# ploza.net
KiCad netlist of a schematic drawn in EAGLE
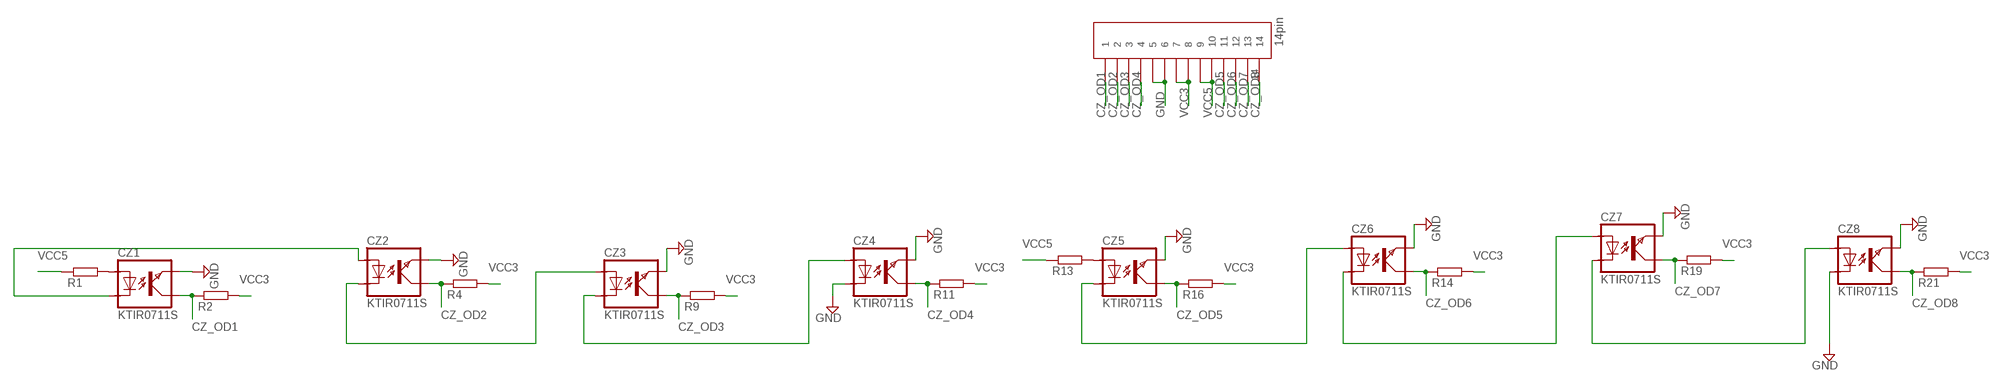
[diagram p0: schematic, sheet 1]

(export (version "E")
  (design (tool "Eeschema 10.0.6"))
  (components
    (comp (ref "CZ1")
      (value "KTIR0711S")
      (footprint "eagle-import:TOP")
      (libsource (lib "eagle-import") (part "KTIR0711S"))
    )
    (comp (ref "CZ2")
      (value "KTIR0711S")
      (footprint "eagle-import:TOP")
      (libsource (lib "eagle-import") (part "KTIR0711S"))
    )
    (comp (ref "CZ3")
      (value "KTIR0711S")
      (footprint "eagle-import:TOP")
      (libsource (lib "eagle-import") (part "KTIR0711S"))
    )
    (comp (ref "CZ4")
      (value "KTIR0711S")
      (footprint "eagle-import:TOP")
      (libsource (lib "eagle-import") (part "KTIR0711S"))
    )
    (comp (ref "CZ5")
      (value "KTIR0711S")
      (footprint "eagle-import:TOP")
      (libsource (lib "eagle-import") (part "KTIR0711S"))
    )
    (comp (ref "CZ6")
      (value "KTIR0711S")
      (footprint "eagle-import:TOP")
      (libsource (lib "eagle-import") (part "KTIR0711S"))
    )
    (comp (ref "CZ7")
      (value "KTIR0711S")
      (footprint "eagle-import:TOP")
      (libsource (lib "eagle-import") (part "KTIR0711S"))
    )
    (comp (ref "CZ8")
      (value "KTIR0711S")
      (footprint "eagle-import:TOP")
      (libsource (lib "eagle-import") (part "KTIR0711S"))
    )
    (comp (ref "R1")
      (value "R-EU_R0805")
      (footprint "eagle-import:R0805")
      (libsource (lib "eagle-import") (part "R-EU_R0805"))
    )
    (comp (ref "R2")
      (value "R-EU_R0805")
      (footprint "eagle-import:R0805")
      (libsource (lib "eagle-import") (part "R-EU_R0805"))
    )
    (comp (ref "R4")
      (value "R-EU_R0805")
      (footprint "eagle-import:R0805")
      (libsource (lib "eagle-import") (part "R-EU_R0805"))
    )
    (comp (ref "R9")
      (value "R-EU_R0805")
      (footprint "eagle-import:R0805")
      (libsource (lib "eagle-import") (part "R-EU_R0805"))
    )
    (comp (ref "R11")
      (value "R-EU_R0805")
      (footprint "eagle-import:R0805")
      (libsource (lib "eagle-import") (part "R-EU_R0805"))
    )
    (comp (ref "R13")
      (value "R-EU_R0805")
      (footprint "eagle-import:R0805")
      (libsource (lib "eagle-import") (part "R-EU_R0805"))
    )
    (comp (ref "R14")
      (value "R-EU_R0805")
      (footprint "eagle-import:R0805")
      (libsource (lib "eagle-import") (part "R-EU_R0805"))
    )
    (comp (ref "R16")
      (value "R-EU_R0805")
      (footprint "eagle-import:R0805")
      (libsource (lib "eagle-import") (part "R-EU_R0805"))
    )
    (comp (ref "R19")
      (value "R-EU_R0805")
      (footprint "eagle-import:R0805")
      (libsource (lib "eagle-import") (part "R-EU_R0805"))
    )
    (comp (ref "R21")
      (value "R-EU_R0805")
      (footprint "eagle-import:R0805")
      (libsource (lib "eagle-import") (part "R-EU_R0805"))
    )
    (comp (ref "U$2")
      (value "14PIN")
      (footprint "eagle-import:14PIN")
      (libsource (lib "eagle-import") (part "14PIN"))
    )
  )
  (nets
    (net (code "1") (name "/CZ_OD1") (class "Default")
      (node (ref "CZ1") (pin "KOLEKTOR") (pinfunction "KOLEKTOR_KOLEKTOR") (pintype "bidirectional"))
      (node (ref "R2") (pin "1") (pinfunction "1_1") (pintype "passive"))
      (node (ref "U$2") (pin "1") (pinfunction "1_1") (pintype "bidirectional"))
    )
    (net (code "2") (name "/CZ_OD2") (class "Default")
      (node (ref "CZ2") (pin "KOLEKTOR") (pinfunction "KOLEKTOR_KOLEKTOR") (pintype "bidirectional"))
      (node (ref "R4") (pin "1") (pinfunction "1_1") (pintype "passive"))
      (node (ref "U$2") (pin "2") (pinfunction "2_2") (pintype "bidirectional"))
    )
    (net (code "3") (name "/CZ_OD3") (class "Default")
      (node (ref "CZ3") (pin "KOLEKTOR") (pinfunction "KOLEKTOR_KOLEKTOR") (pintype "bidirectional"))
      (node (ref "R9") (pin "1") (pinfunction "1_1") (pintype "passive"))
      (node (ref "U$2") (pin "3") (pinfunction "3_3") (pintype "bidirectional"))
    )
    (net (code "4") (name "/CZ_OD4") (class "Default")
      (node (ref "CZ4") (pin "KOLEKTOR") (pinfunction "KOLEKTOR_KOLEKTOR") (pintype "bidirectional"))
      (node (ref "R11") (pin "1") (pinfunction "1_1") (pintype "passive"))
      (node (ref "U$2") (pin "4") (pinfunction "4_4") (pintype "bidirectional"))
    )
    (net (code "5") (name "/CZ_OD5") (class "Default")
      (node (ref "CZ5") (pin "KOLEKTOR") (pinfunction "KOLEKTOR_KOLEKTOR") (pintype "bidirectional"))
      (node (ref "R16") (pin "1") (pinfunction "1_1") (pintype "passive"))
      (node (ref "U$2") (pin "11") (pinfunction "11_11") (pintype "bidirectional"))
    )
    (net (code "6") (name "/CZ_OD6") (class "Default")
      (node (ref "CZ6") (pin "KOLEKTOR") (pinfunction "KOLEKTOR_KOLEKTOR") (pintype "bidirectional"))
      (node (ref "R14") (pin "1") (pinfunction "1_1") (pintype "passive"))
      (node (ref "U$2") (pin "12") (pinfunction "12_12") (pintype "bidirectional"))
    )
    (net (code "7") (name "/CZ_OD7") (class "Default")
      (node (ref "CZ7") (pin "KOLEKTOR") (pinfunction "KOLEKTOR_KOLEKTOR") (pintype "bidirectional"))
      (node (ref "R19") (pin "1") (pinfunction "1_1") (pintype "passive"))
      (node (ref "U$2") (pin "13") (pinfunction "13_13") (pintype "bidirectional"))
    )
    (net (code "8") (name "/CZ_OD8") (class "Default")
      (node (ref "CZ8") (pin "KOLEKTOR") (pinfunction "KOLEKTOR_KOLEKTOR") (pintype "bidirectional"))
      (node (ref "R21") (pin "1") (pinfunction "1_1") (pintype "passive"))
      (node (ref "U$2") (pin "14") (pinfunction "14_14") (pintype "bidirectional"))
    )
    (net (code "9") (name "/VCC3") (class "Default")
      (node (ref "R11") (pin "2") (pinfunction "2_2") (pintype "passive"))
      (node (ref "R14") (pin "2") (pinfunction "2_2") (pintype "passive"))
      (node (ref "R16") (pin "2") (pinfunction "2_2") (pintype "passive"))
      (node (ref "R19") (pin "2") (pinfunction "2_2") (pintype "passive"))
      (node (ref "R2") (pin "2") (pinfunction "2_2") (pintype "passive"))
      (node (ref "R21") (pin "2") (pinfunction "2_2") (pintype "passive"))
      (node (ref "R4") (pin "2") (pinfunction "2_2") (pintype "passive"))
      (node (ref "R9") (pin "2") (pinfunction "2_2") (pintype "passive"))
      (node (ref "U$2") (pin "7") (pinfunction "7_7") (pintype "bidirectional"))
      (node (ref "U$2") (pin "8") (pinfunction "8_8") (pintype "bidirectional"))
    )
    (net (code "10") (name "/VCC5") (class "Default")
      (node (ref "R1") (pin "1") (pinfunction "1_1") (pintype "passive"))
      (node (ref "R13") (pin "1") (pinfunction "1_1") (pintype "passive"))
      (node (ref "U$2") (pin "10") (pinfunction "10_10") (pintype "bidirectional"))
      (node (ref "U$2") (pin "9") (pinfunction "9_9") (pintype "bidirectional"))
    )
    (net (code "11") (name "GND") (class "Default")
      (node (ref "CZ1") (pin "EMITER") (pinfunction "EMITER_EMITER") (pintype "bidirectional"))
      (node (ref "CZ2") (pin "EMITER") (pinfunction "EMITER_EMITER") (pintype "bidirectional"))
      (node (ref "CZ3") (pin "EMITER") (pinfunction "EMITER_EMITER") (pintype "bidirectional"))
      (node (ref "CZ4") (pin "EMITER") (pinfunction "EMITER_EMITER") (pintype "bidirectional"))
      (node (ref "CZ4") (pin "KATODA") (pinfunction "KATODA_KATODA") (pintype "passive"))
      (node (ref "CZ5") (pin "EMITER") (pinfunction "EMITER_EMITER") (pintype "bidirectional"))
      (node (ref "CZ6") (pin "EMITER") (pinfunction "EMITER_EMITER") (pintype "bidirectional"))
      (node (ref "CZ7") (pin "EMITER") (pinfunction "EMITER_EMITER") (pintype "bidirectional"))
      (node (ref "CZ8") (pin "EMITER") (pinfunction "EMITER_EMITER") (pintype "bidirectional"))
      (node (ref "CZ8") (pin "KATODA") (pinfunction "KATODA_KATODA") (pintype "passive"))
      (node (ref "U$2") (pin "5") (pinfunction "5_5") (pintype "bidirectional"))
      (node (ref "U$2") (pin "6") (pinfunction "6_6") (pintype "bidirectional"))
    )
    (net (code "12") (name "Net-(CZ1-PadANODA)") (class "Default")
      (node (ref "CZ1") (pin "ANODA") (pinfunction "ANODA_ANODA") (pintype "passive"))
      (node (ref "R1") (pin "2") (pinfunction "2_2") (pintype "passive"))
    )
    (net (code "13") (name "Net-(CZ1-PadKATODA)") (class "Default")
      (node (ref "CZ1") (pin "KATODA") (pinfunction "KATODA_KATODA") (pintype "passive"))
      (node (ref "CZ2") (pin "ANODA") (pinfunction "ANODA_ANODA") (pintype "passive"))
    )
    (net (code "14") (name "Net-(CZ2-PadKATODA)") (class "Default")
      (node (ref "CZ2") (pin "KATODA") (pinfunction "KATODA_KATODA") (pintype "passive"))
      (node (ref "CZ3") (pin "ANODA") (pinfunction "ANODA_ANODA") (pintype "passive"))
    )
    (net (code "15") (name "Net-(CZ3-PadKATODA)") (class "Default")
      (node (ref "CZ3") (pin "KATODA") (pinfunction "KATODA_KATODA") (pintype "passive"))
      (node (ref "CZ4") (pin "ANODA") (pinfunction "ANODA_ANODA") (pintype "passive"))
    )
    (net (code "16") (name "Net-(CZ5-PadANODA)") (class "Default")
      (node (ref "CZ5") (pin "ANODA") (pinfunction "ANODA_ANODA") (pintype "passive"))
      (node (ref "R13") (pin "2") (pinfunction "2_2") (pintype "passive"))
    )
    (net (code "17") (name "Net-(CZ5-PadKATODA)") (class "Default")
      (node (ref "CZ5") (pin "KATODA") (pinfunction "KATODA_KATODA") (pintype "passive"))
      (node (ref "CZ6") (pin "ANODA") (pinfunction "ANODA_ANODA") (pintype "passive"))
    )
    (net (code "18") (name "Net-(CZ6-PadKATODA)") (class "Default")
      (node (ref "CZ6") (pin "KATODA") (pinfunction "KATODA_KATODA") (pintype "passive"))
      (node (ref "CZ7") (pin "ANODA") (pinfunction "ANODA_ANODA") (pintype "passive"))
    )
    (net (code "19") (name "Net-(CZ7-PadKATODA)") (class "Default")
      (node (ref "CZ7") (pin "KATODA") (pinfunction "KATODA_KATODA") (pintype "passive"))
      (node (ref "CZ8") (pin "ANODA") (pinfunction "ANODA_ANODA") (pintype "passive"))
    )
  )
)
